# 20210526-8-channel-solid-relay.net
KiCad netlist of a schematic drawn in EasyEDA
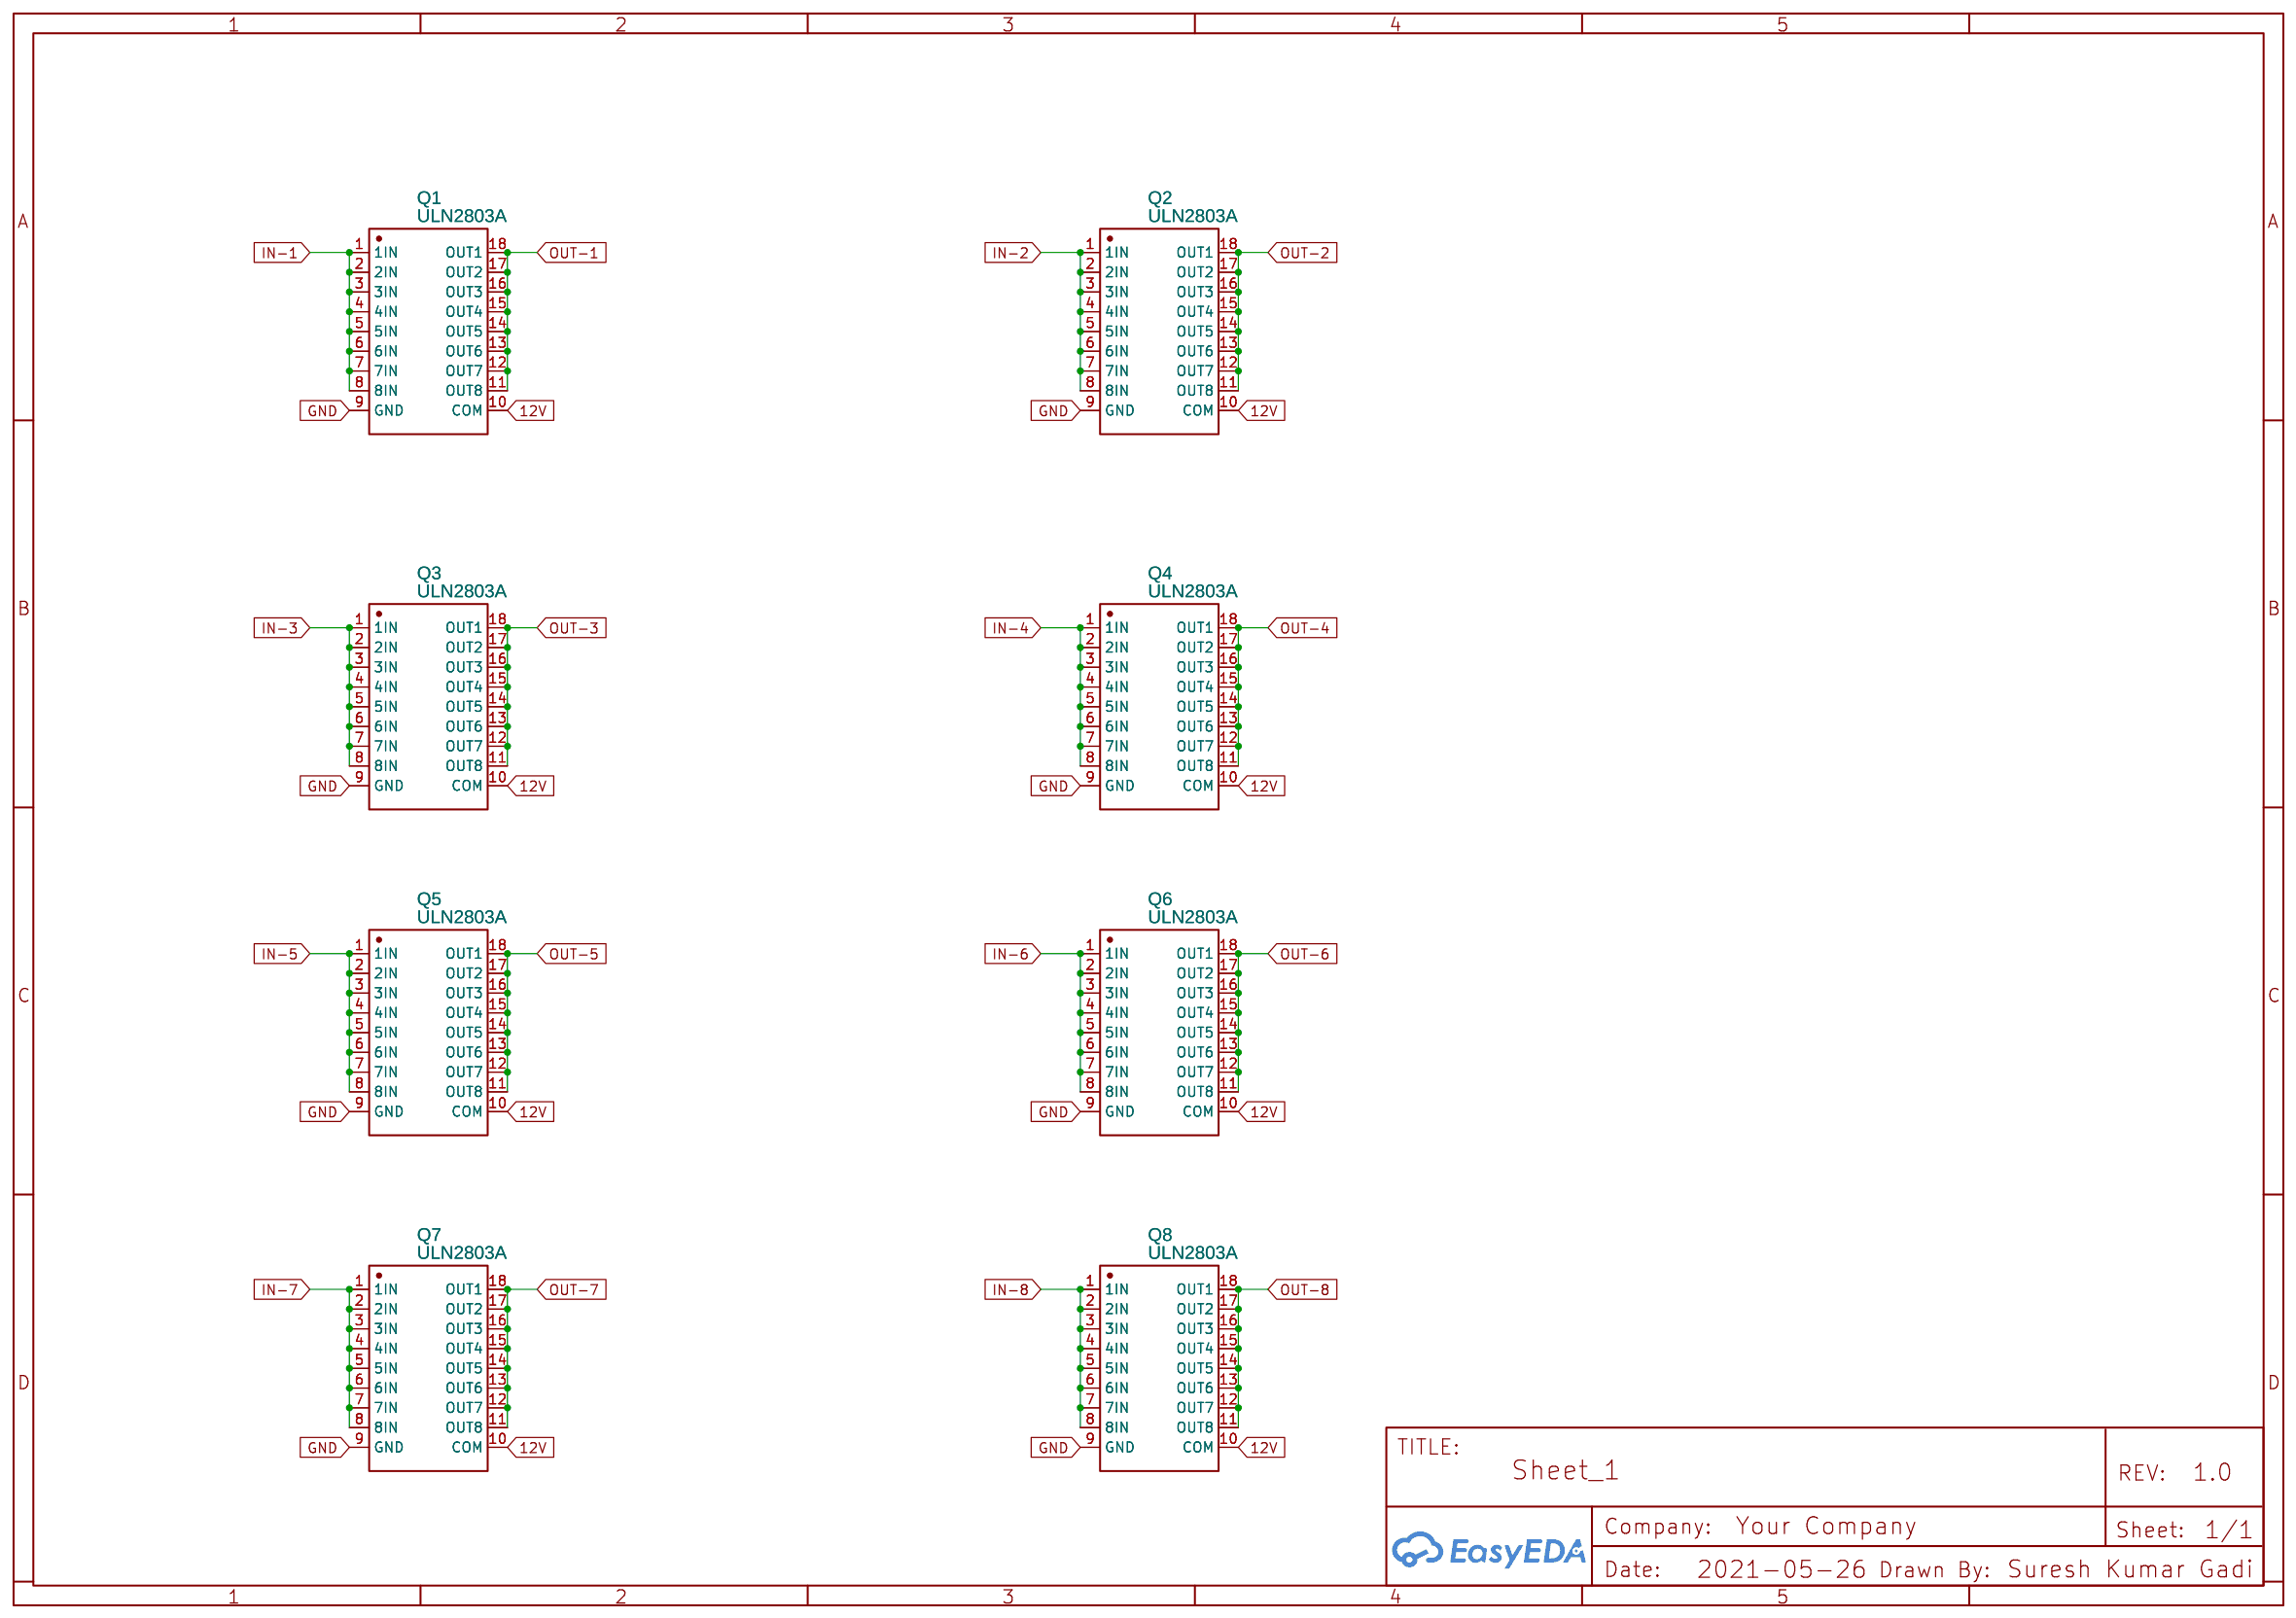
[diagram p0: SolidRelays]
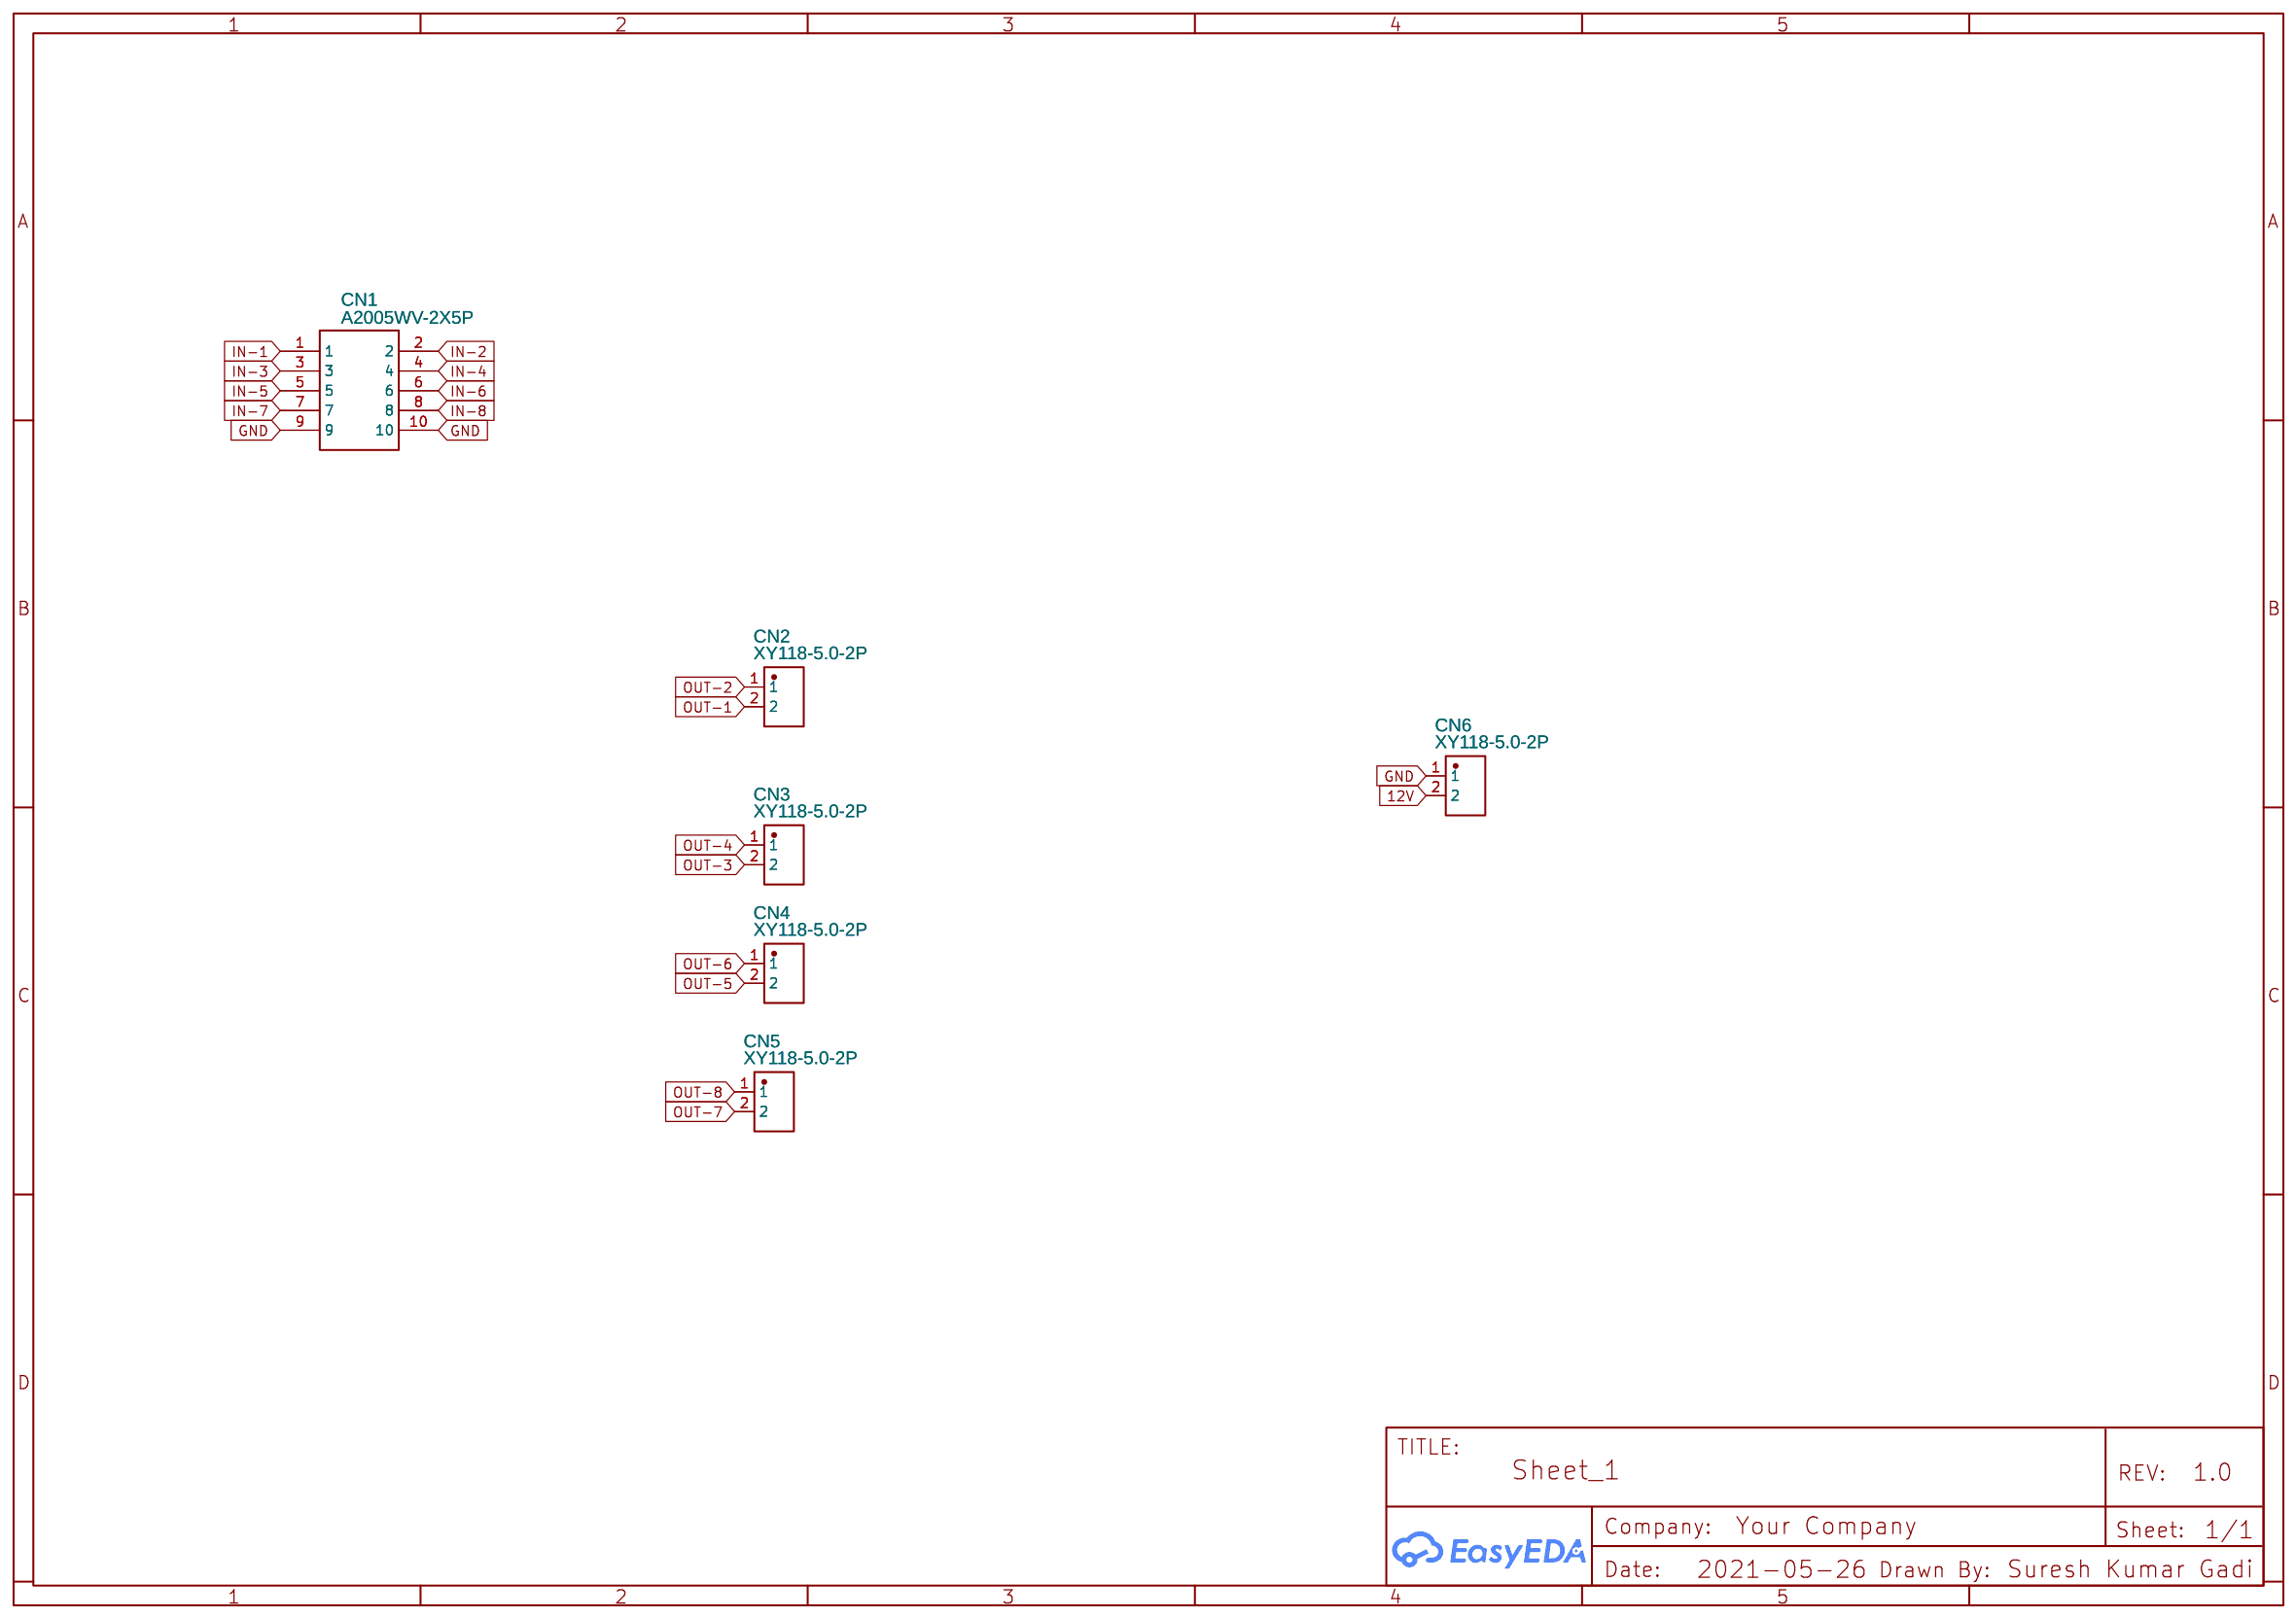
[diagram p1: Connectors]

(export (version "E")
  (design (tool "Eeschema 10.0.6"))
  (components
    (comp (ref "Q1")
      (value "ULN2803A")
      (fields (field (name "BOM_Supplier Part") "C73936"))
      (libsource (lib "") (part "ULN2803A"))
    )
    (comp (ref "Q2")
      (value "ULN2803A")
      (fields (field (name "BOM_Supplier Part") "C73936"))
      (libsource (lib "") (part "ULN2803A"))
    )
    (comp (ref "Q3")
      (value "ULN2803A")
      (fields (field (name "BOM_Supplier Part") "C73936"))
      (libsource (lib "") (part "ULN2803A"))
    )
    (comp (ref "Q4")
      (value "ULN2803A")
      (fields (field (name "BOM_Supplier Part") "C73936"))
      (libsource (lib "") (part "ULN2803A"))
    )
    (comp (ref "Q5")
      (value "ULN2803A")
      (fields (field (name "BOM_Supplier Part") "C73936"))
      (libsource (lib "") (part "ULN2803A"))
    )
    (comp (ref "Q6")
      (value "ULN2803A")
      (fields (field (name "BOM_Supplier Part") "C73936"))
      (libsource (lib "") (part "ULN2803A"))
    )
    (comp (ref "Q7")
      (value "ULN2803A")
      (fields (field (name "BOM_Supplier Part") "C73936"))
      (libsource (lib "") (part "ULN2803A"))
    )
    (comp (ref "Q8")
      (value "ULN2803A")
      (fields (field (name "BOM_Supplier Part") "C73936"))
      (libsource (lib "") (part "ULN2803A"))
    )
    (comp (ref "CN1")
      (value "A2005WV-2X5P")
      (fields
        (field (name "BOM_Manufacturer Part") "A2005WV-2x5P")
        (field (name "BOM_Supplier Part") "C225290")
      )
      (libsource (lib "") (part "A2005WV-2X5P"))
    )
    (comp (ref "CN2")
      (value "XY118-5.0-2P")
      (fields (field (name "BOM_Supplier Part") "C784922"))
      (libsource (lib "") (part "XY118-5.0-2P"))
    )
    (comp (ref "CN3")
      (value "XY118-5.0-2P")
      (fields (field (name "BOM_Supplier Part") "C784922"))
      (libsource (lib "") (part "XY118-5.0-2P"))
    )
    (comp (ref "CN4")
      (value "XY118-5.0-2P")
      (fields (field (name "BOM_Supplier Part") "C784922"))
      (libsource (lib "") (part "XY118-5.0-2P"))
    )
    (comp (ref "CN5")
      (value "XY118-5.0-2P")
      (fields (field (name "BOM_Supplier Part") "C784922"))
      (libsource (lib "") (part "XY118-5.0-2P"))
    )
    (comp (ref "CN6")
      (value "XY118-5.0-2P")
      (fields (field (name "BOM_Supplier Part") "C784922"))
      (libsource (lib "") (part "XY118-5.0-2P"))
    )
  )
  (nets
    (net (code "1") (name "12V") (class "Default")
      (node (ref "CN6") (pin "2") (pinfunction "2_2") (pintype "unspecified"))
      (node (ref "Q1") (pin "10") (pinfunction "COM_10") (pintype "unspecified"))
      (node (ref "Q2") (pin "10") (pinfunction "COM_10") (pintype "unspecified"))
      (node (ref "Q3") (pin "10") (pinfunction "COM_10") (pintype "unspecified"))
      (node (ref "Q4") (pin "10") (pinfunction "COM_10") (pintype "unspecified"))
      (node (ref "Q5") (pin "10") (pinfunction "COM_10") (pintype "unspecified"))
      (node (ref "Q6") (pin "10") (pinfunction "COM_10") (pintype "unspecified"))
      (node (ref "Q7") (pin "10") (pinfunction "COM_10") (pintype "unspecified"))
      (node (ref "Q8") (pin "10") (pinfunction "COM_10") (pintype "unspecified"))
    )
    (net (code "2") (name "GND") (class "Default")
      (node (ref "CN1") (pin "10") (pinfunction "10_10") (pintype "unspecified"))
      (node (ref "CN1") (pin "9") (pinfunction "9_9") (pintype "unspecified"))
      (node (ref "CN6") (pin "1") (pinfunction "1_1") (pintype "unspecified"))
      (node (ref "Q1") (pin "9") (pinfunction "GND_9") (pintype "unspecified"))
      (node (ref "Q2") (pin "9") (pinfunction "GND_9") (pintype "unspecified"))
      (node (ref "Q3") (pin "9") (pinfunction "GND_9") (pintype "unspecified"))
      (node (ref "Q4") (pin "9") (pinfunction "GND_9") (pintype "unspecified"))
      (node (ref "Q5") (pin "9") (pinfunction "GND_9") (pintype "unspecified"))
      (node (ref "Q6") (pin "9") (pinfunction "GND_9") (pintype "unspecified"))
      (node (ref "Q7") (pin "9") (pinfunction "GND_9") (pintype "unspecified"))
      (node (ref "Q8") (pin "9") (pinfunction "GND_9") (pintype "unspecified"))
    )
    (net (code "3") (name "IN-1") (class "Default")
      (node (ref "CN1") (pin "1") (pinfunction "1_1") (pintype "unspecified"))
      (node (ref "Q1") (pin "1") (pinfunction "1IN_1") (pintype "unspecified"))
      (node (ref "Q1") (pin "2") (pinfunction "2IN_2") (pintype "unspecified"))
      (node (ref "Q1") (pin "3") (pinfunction "3IN_3") (pintype "unspecified"))
      (node (ref "Q1") (pin "4") (pinfunction "4IN_4") (pintype "unspecified"))
      (node (ref "Q1") (pin "5") (pinfunction "5IN_5") (pintype "unspecified"))
      (node (ref "Q1") (pin "6") (pinfunction "6IN_6") (pintype "unspecified"))
      (node (ref "Q1") (pin "7") (pinfunction "7IN_7") (pintype "unspecified"))
      (node (ref "Q1") (pin "8") (pinfunction "8IN_8") (pintype "unspecified"))
    )
    (net (code "4") (name "IN-2") (class "Default")
      (node (ref "CN1") (pin "2") (pinfunction "2_2") (pintype "unspecified"))
      (node (ref "Q2") (pin "1") (pinfunction "1IN_1") (pintype "unspecified"))
      (node (ref "Q2") (pin "2") (pinfunction "2IN_2") (pintype "unspecified"))
      (node (ref "Q2") (pin "3") (pinfunction "3IN_3") (pintype "unspecified"))
      (node (ref "Q2") (pin "4") (pinfunction "4IN_4") (pintype "unspecified"))
      (node (ref "Q2") (pin "5") (pinfunction "5IN_5") (pintype "unspecified"))
      (node (ref "Q2") (pin "6") (pinfunction "6IN_6") (pintype "unspecified"))
      (node (ref "Q2") (pin "7") (pinfunction "7IN_7") (pintype "unspecified"))
      (node (ref "Q2") (pin "8") (pinfunction "8IN_8") (pintype "unspecified"))
    )
    (net (code "5") (name "IN-3") (class "Default")
      (node (ref "CN1") (pin "3") (pinfunction "3_3") (pintype "unspecified"))
      (node (ref "Q3") (pin "1") (pinfunction "1IN_1") (pintype "unspecified"))
      (node (ref "Q3") (pin "2") (pinfunction "2IN_2") (pintype "unspecified"))
      (node (ref "Q3") (pin "3") (pinfunction "3IN_3") (pintype "unspecified"))
      (node (ref "Q3") (pin "4") (pinfunction "4IN_4") (pintype "unspecified"))
      (node (ref "Q3") (pin "5") (pinfunction "5IN_5") (pintype "unspecified"))
      (node (ref "Q3") (pin "6") (pinfunction "6IN_6") (pintype "unspecified"))
      (node (ref "Q3") (pin "7") (pinfunction "7IN_7") (pintype "unspecified"))
      (node (ref "Q3") (pin "8") (pinfunction "8IN_8") (pintype "unspecified"))
    )
    (net (code "6") (name "IN-4") (class "Default")
      (node (ref "CN1") (pin "4") (pinfunction "4_4") (pintype "unspecified"))
      (node (ref "Q4") (pin "1") (pinfunction "1IN_1") (pintype "unspecified"))
      (node (ref "Q4") (pin "2") (pinfunction "2IN_2") (pintype "unspecified"))
      (node (ref "Q4") (pin "3") (pinfunction "3IN_3") (pintype "unspecified"))
      (node (ref "Q4") (pin "4") (pinfunction "4IN_4") (pintype "unspecified"))
      (node (ref "Q4") (pin "5") (pinfunction "5IN_5") (pintype "unspecified"))
      (node (ref "Q4") (pin "6") (pinfunction "6IN_6") (pintype "unspecified"))
      (node (ref "Q4") (pin "7") (pinfunction "7IN_7") (pintype "unspecified"))
      (node (ref "Q4") (pin "8") (pinfunction "8IN_8") (pintype "unspecified"))
    )
    (net (code "7") (name "IN-5") (class "Default")
      (node (ref "CN1") (pin "5") (pinfunction "5_5") (pintype "unspecified"))
      (node (ref "Q5") (pin "1") (pinfunction "1IN_1") (pintype "unspecified"))
      (node (ref "Q5") (pin "2") (pinfunction "2IN_2") (pintype "unspecified"))
      (node (ref "Q5") (pin "3") (pinfunction "3IN_3") (pintype "unspecified"))
      (node (ref "Q5") (pin "4") (pinfunction "4IN_4") (pintype "unspecified"))
      (node (ref "Q5") (pin "5") (pinfunction "5IN_5") (pintype "unspecified"))
      (node (ref "Q5") (pin "6") (pinfunction "6IN_6") (pintype "unspecified"))
      (node (ref "Q5") (pin "7") (pinfunction "7IN_7") (pintype "unspecified"))
      (node (ref "Q5") (pin "8") (pinfunction "8IN_8") (pintype "unspecified"))
    )
    (net (code "8") (name "IN-6") (class "Default")
      (node (ref "CN1") (pin "6") (pinfunction "6_6") (pintype "unspecified"))
      (node (ref "Q6") (pin "1") (pinfunction "1IN_1") (pintype "unspecified"))
      (node (ref "Q6") (pin "2") (pinfunction "2IN_2") (pintype "unspecified"))
      (node (ref "Q6") (pin "3") (pinfunction "3IN_3") (pintype "unspecified"))
      (node (ref "Q6") (pin "4") (pinfunction "4IN_4") (pintype "unspecified"))
      (node (ref "Q6") (pin "5") (pinfunction "5IN_5") (pintype "unspecified"))
      (node (ref "Q6") (pin "6") (pinfunction "6IN_6") (pintype "unspecified"))
      (node (ref "Q6") (pin "7") (pinfunction "7IN_7") (pintype "unspecified"))
      (node (ref "Q6") (pin "8") (pinfunction "8IN_8") (pintype "unspecified"))
    )
    (net (code "9") (name "IN-7") (class "Default")
      (node (ref "CN1") (pin "7") (pinfunction "7_7") (pintype "unspecified"))
      (node (ref "Q7") (pin "1") (pinfunction "1IN_1") (pintype "unspecified"))
      (node (ref "Q7") (pin "2") (pinfunction "2IN_2") (pintype "unspecified"))
      (node (ref "Q7") (pin "3") (pinfunction "3IN_3") (pintype "unspecified"))
      (node (ref "Q7") (pin "4") (pinfunction "4IN_4") (pintype "unspecified"))
      (node (ref "Q7") (pin "5") (pinfunction "5IN_5") (pintype "unspecified"))
      (node (ref "Q7") (pin "6") (pinfunction "6IN_6") (pintype "unspecified"))
      (node (ref "Q7") (pin "7") (pinfunction "7IN_7") (pintype "unspecified"))
      (node (ref "Q7") (pin "8") (pinfunction "8IN_8") (pintype "unspecified"))
    )
    (net (code "10") (name "IN-8") (class "Default")
      (node (ref "CN1") (pin "8") (pinfunction "8_8") (pintype "unspecified"))
      (node (ref "Q8") (pin "1") (pinfunction "1IN_1") (pintype "unspecified"))
      (node (ref "Q8") (pin "2") (pinfunction "2IN_2") (pintype "unspecified"))
      (node (ref "Q8") (pin "3") (pinfunction "3IN_3") (pintype "unspecified"))
      (node (ref "Q8") (pin "4") (pinfunction "4IN_4") (pintype "unspecified"))
      (node (ref "Q8") (pin "5") (pinfunction "5IN_5") (pintype "unspecified"))
      (node (ref "Q8") (pin "6") (pinfunction "6IN_6") (pintype "unspecified"))
      (node (ref "Q8") (pin "7") (pinfunction "7IN_7") (pintype "unspecified"))
      (node (ref "Q8") (pin "8") (pinfunction "8IN_8") (pintype "unspecified"))
    )
    (net (code "11") (name "OUT-1") (class "Default")
      (node (ref "CN2") (pin "2") (pinfunction "2_2") (pintype "unspecified"))
      (node (ref "Q1") (pin "11") (pinfunction "OUT8_11") (pintype "unspecified"))
      (node (ref "Q1") (pin "12") (pinfunction "OUT7_12") (pintype "unspecified"))
      (node (ref "Q1") (pin "13") (pinfunction "OUT6_13") (pintype "unspecified"))
      (node (ref "Q1") (pin "14") (pinfunction "OUT5_14") (pintype "unspecified"))
      (node (ref "Q1") (pin "15") (pinfunction "OUT4_15") (pintype "unspecified"))
      (node (ref "Q1") (pin "16") (pinfunction "OUT3_16") (pintype "unspecified"))
      (node (ref "Q1") (pin "17") (pinfunction "OUT2_17") (pintype "unspecified"))
      (node (ref "Q1") (pin "18") (pinfunction "OUT1_18") (pintype "unspecified"))
    )
    (net (code "12") (name "OUT-2") (class "Default")
      (node (ref "CN2") (pin "1") (pinfunction "1_1") (pintype "unspecified"))
      (node (ref "Q2") (pin "11") (pinfunction "OUT8_11") (pintype "unspecified"))
      (node (ref "Q2") (pin "12") (pinfunction "OUT7_12") (pintype "unspecified"))
      (node (ref "Q2") (pin "13") (pinfunction "OUT6_13") (pintype "unspecified"))
      (node (ref "Q2") (pin "14") (pinfunction "OUT5_14") (pintype "unspecified"))
      (node (ref "Q2") (pin "15") (pinfunction "OUT4_15") (pintype "unspecified"))
      (node (ref "Q2") (pin "16") (pinfunction "OUT3_16") (pintype "unspecified"))
      (node (ref "Q2") (pin "17") (pinfunction "OUT2_17") (pintype "unspecified"))
      (node (ref "Q2") (pin "18") (pinfunction "OUT1_18") (pintype "unspecified"))
    )
    (net (code "13") (name "OUT-3") (class "Default")
      (node (ref "CN3") (pin "2") (pinfunction "2_2") (pintype "unspecified"))
      (node (ref "Q3") (pin "11") (pinfunction "OUT8_11") (pintype "unspecified"))
      (node (ref "Q3") (pin "12") (pinfunction "OUT7_12") (pintype "unspecified"))
      (node (ref "Q3") (pin "13") (pinfunction "OUT6_13") (pintype "unspecified"))
      (node (ref "Q3") (pin "14") (pinfunction "OUT5_14") (pintype "unspecified"))
      (node (ref "Q3") (pin "15") (pinfunction "OUT4_15") (pintype "unspecified"))
      (node (ref "Q3") (pin "16") (pinfunction "OUT3_16") (pintype "unspecified"))
      (node (ref "Q3") (pin "17") (pinfunction "OUT2_17") (pintype "unspecified"))
      (node (ref "Q3") (pin "18") (pinfunction "OUT1_18") (pintype "unspecified"))
    )
    (net (code "14") (name "OUT-4") (class "Default")
      (node (ref "CN3") (pin "1") (pinfunction "1_1") (pintype "unspecified"))
      (node (ref "Q4") (pin "11") (pinfunction "OUT8_11") (pintype "unspecified"))
      (node (ref "Q4") (pin "12") (pinfunction "OUT7_12") (pintype "unspecified"))
      (node (ref "Q4") (pin "13") (pinfunction "OUT6_13") (pintype "unspecified"))
      (node (ref "Q4") (pin "14") (pinfunction "OUT5_14") (pintype "unspecified"))
      (node (ref "Q4") (pin "15") (pinfunction "OUT4_15") (pintype "unspecified"))
      (node (ref "Q4") (pin "16") (pinfunction "OUT3_16") (pintype "unspecified"))
      (node (ref "Q4") (pin "17") (pinfunction "OUT2_17") (pintype "unspecified"))
      (node (ref "Q4") (pin "18") (pinfunction "OUT1_18") (pintype "unspecified"))
    )
    (net (code "15") (name "OUT-5") (class "Default")
      (node (ref "CN4") (pin "2") (pinfunction "2_2") (pintype "unspecified"))
      (node (ref "Q5") (pin "11") (pinfunction "OUT8_11") (pintype "unspecified"))
      (node (ref "Q5") (pin "12") (pinfunction "OUT7_12") (pintype "unspecified"))
      (node (ref "Q5") (pin "13") (pinfunction "OUT6_13") (pintype "unspecified"))
      (node (ref "Q5") (pin "14") (pinfunction "OUT5_14") (pintype "unspecified"))
      (node (ref "Q5") (pin "15") (pinfunction "OUT4_15") (pintype "unspecified"))
      (node (ref "Q5") (pin "16") (pinfunction "OUT3_16") (pintype "unspecified"))
      (node (ref "Q5") (pin "17") (pinfunction "OUT2_17") (pintype "unspecified"))
      (node (ref "Q5") (pin "18") (pinfunction "OUT1_18") (pintype "unspecified"))
    )
    (net (code "16") (name "OUT-6") (class "Default")
      (node (ref "CN4") (pin "1") (pinfunction "1_1") (pintype "unspecified"))
      (node (ref "Q6") (pin "11") (pinfunction "OUT8_11") (pintype "unspecified"))
      (node (ref "Q6") (pin "12") (pinfunction "OUT7_12") (pintype "unspecified"))
      (node (ref "Q6") (pin "13") (pinfunction "OUT6_13") (pintype "unspecified"))
      (node (ref "Q6") (pin "14") (pinfunction "OUT5_14") (pintype "unspecified"))
      (node (ref "Q6") (pin "15") (pinfunction "OUT4_15") (pintype "unspecified"))
      (node (ref "Q6") (pin "16") (pinfunction "OUT3_16") (pintype "unspecified"))
      (node (ref "Q6") (pin "17") (pinfunction "OUT2_17") (pintype "unspecified"))
      (node (ref "Q6") (pin "18") (pinfunction "OUT1_18") (pintype "unspecified"))
    )
    (net (code "17") (name "OUT-7") (class "Default")
      (node (ref "CN5") (pin "2") (pinfunction "2_2") (pintype "unspecified"))
      (node (ref "Q7") (pin "11") (pinfunction "OUT8_11") (pintype "unspecified"))
      (node (ref "Q7") (pin "12") (pinfunction "OUT7_12") (pintype "unspecified"))
      (node (ref "Q7") (pin "13") (pinfunction "OUT6_13") (pintype "unspecified"))
      (node (ref "Q7") (pin "14") (pinfunction "OUT5_14") (pintype "unspecified"))
      (node (ref "Q7") (pin "15") (pinfunction "OUT4_15") (pintype "unspecified"))
      (node (ref "Q7") (pin "16") (pinfunction "OUT3_16") (pintype "unspecified"))
      (node (ref "Q7") (pin "17") (pinfunction "OUT2_17") (pintype "unspecified"))
      (node (ref "Q7") (pin "18") (pinfunction "OUT1_18") (pintype "unspecified"))
    )
    (net (code "18") (name "OUT-8") (class "Default")
      (node (ref "CN5") (pin "1") (pinfunction "1_1") (pintype "unspecified"))
      (node (ref "Q8") (pin "11") (pinfunction "OUT8_11") (pintype "unspecified"))
      (node (ref "Q8") (pin "12") (pinfunction "OUT7_12") (pintype "unspecified"))
      (node (ref "Q8") (pin "13") (pinfunction "OUT6_13") (pintype "unspecified"))
      (node (ref "Q8") (pin "14") (pinfunction "OUT5_14") (pintype "unspecified"))
      (node (ref "Q8") (pin "15") (pinfunction "OUT4_15") (pintype "unspecified"))
      (node (ref "Q8") (pin "16") (pinfunction "OUT3_16") (pintype "unspecified"))
      (node (ref "Q8") (pin "17") (pinfunction "OUT2_17") (pintype "unspecified"))
      (node (ref "Q8") (pin "18") (pinfunction "OUT1_18") (pintype "unspecified"))
    )
  )
)
